# Patch-Prop.net
KiCad netlist of a schematic drawn in EAGLE
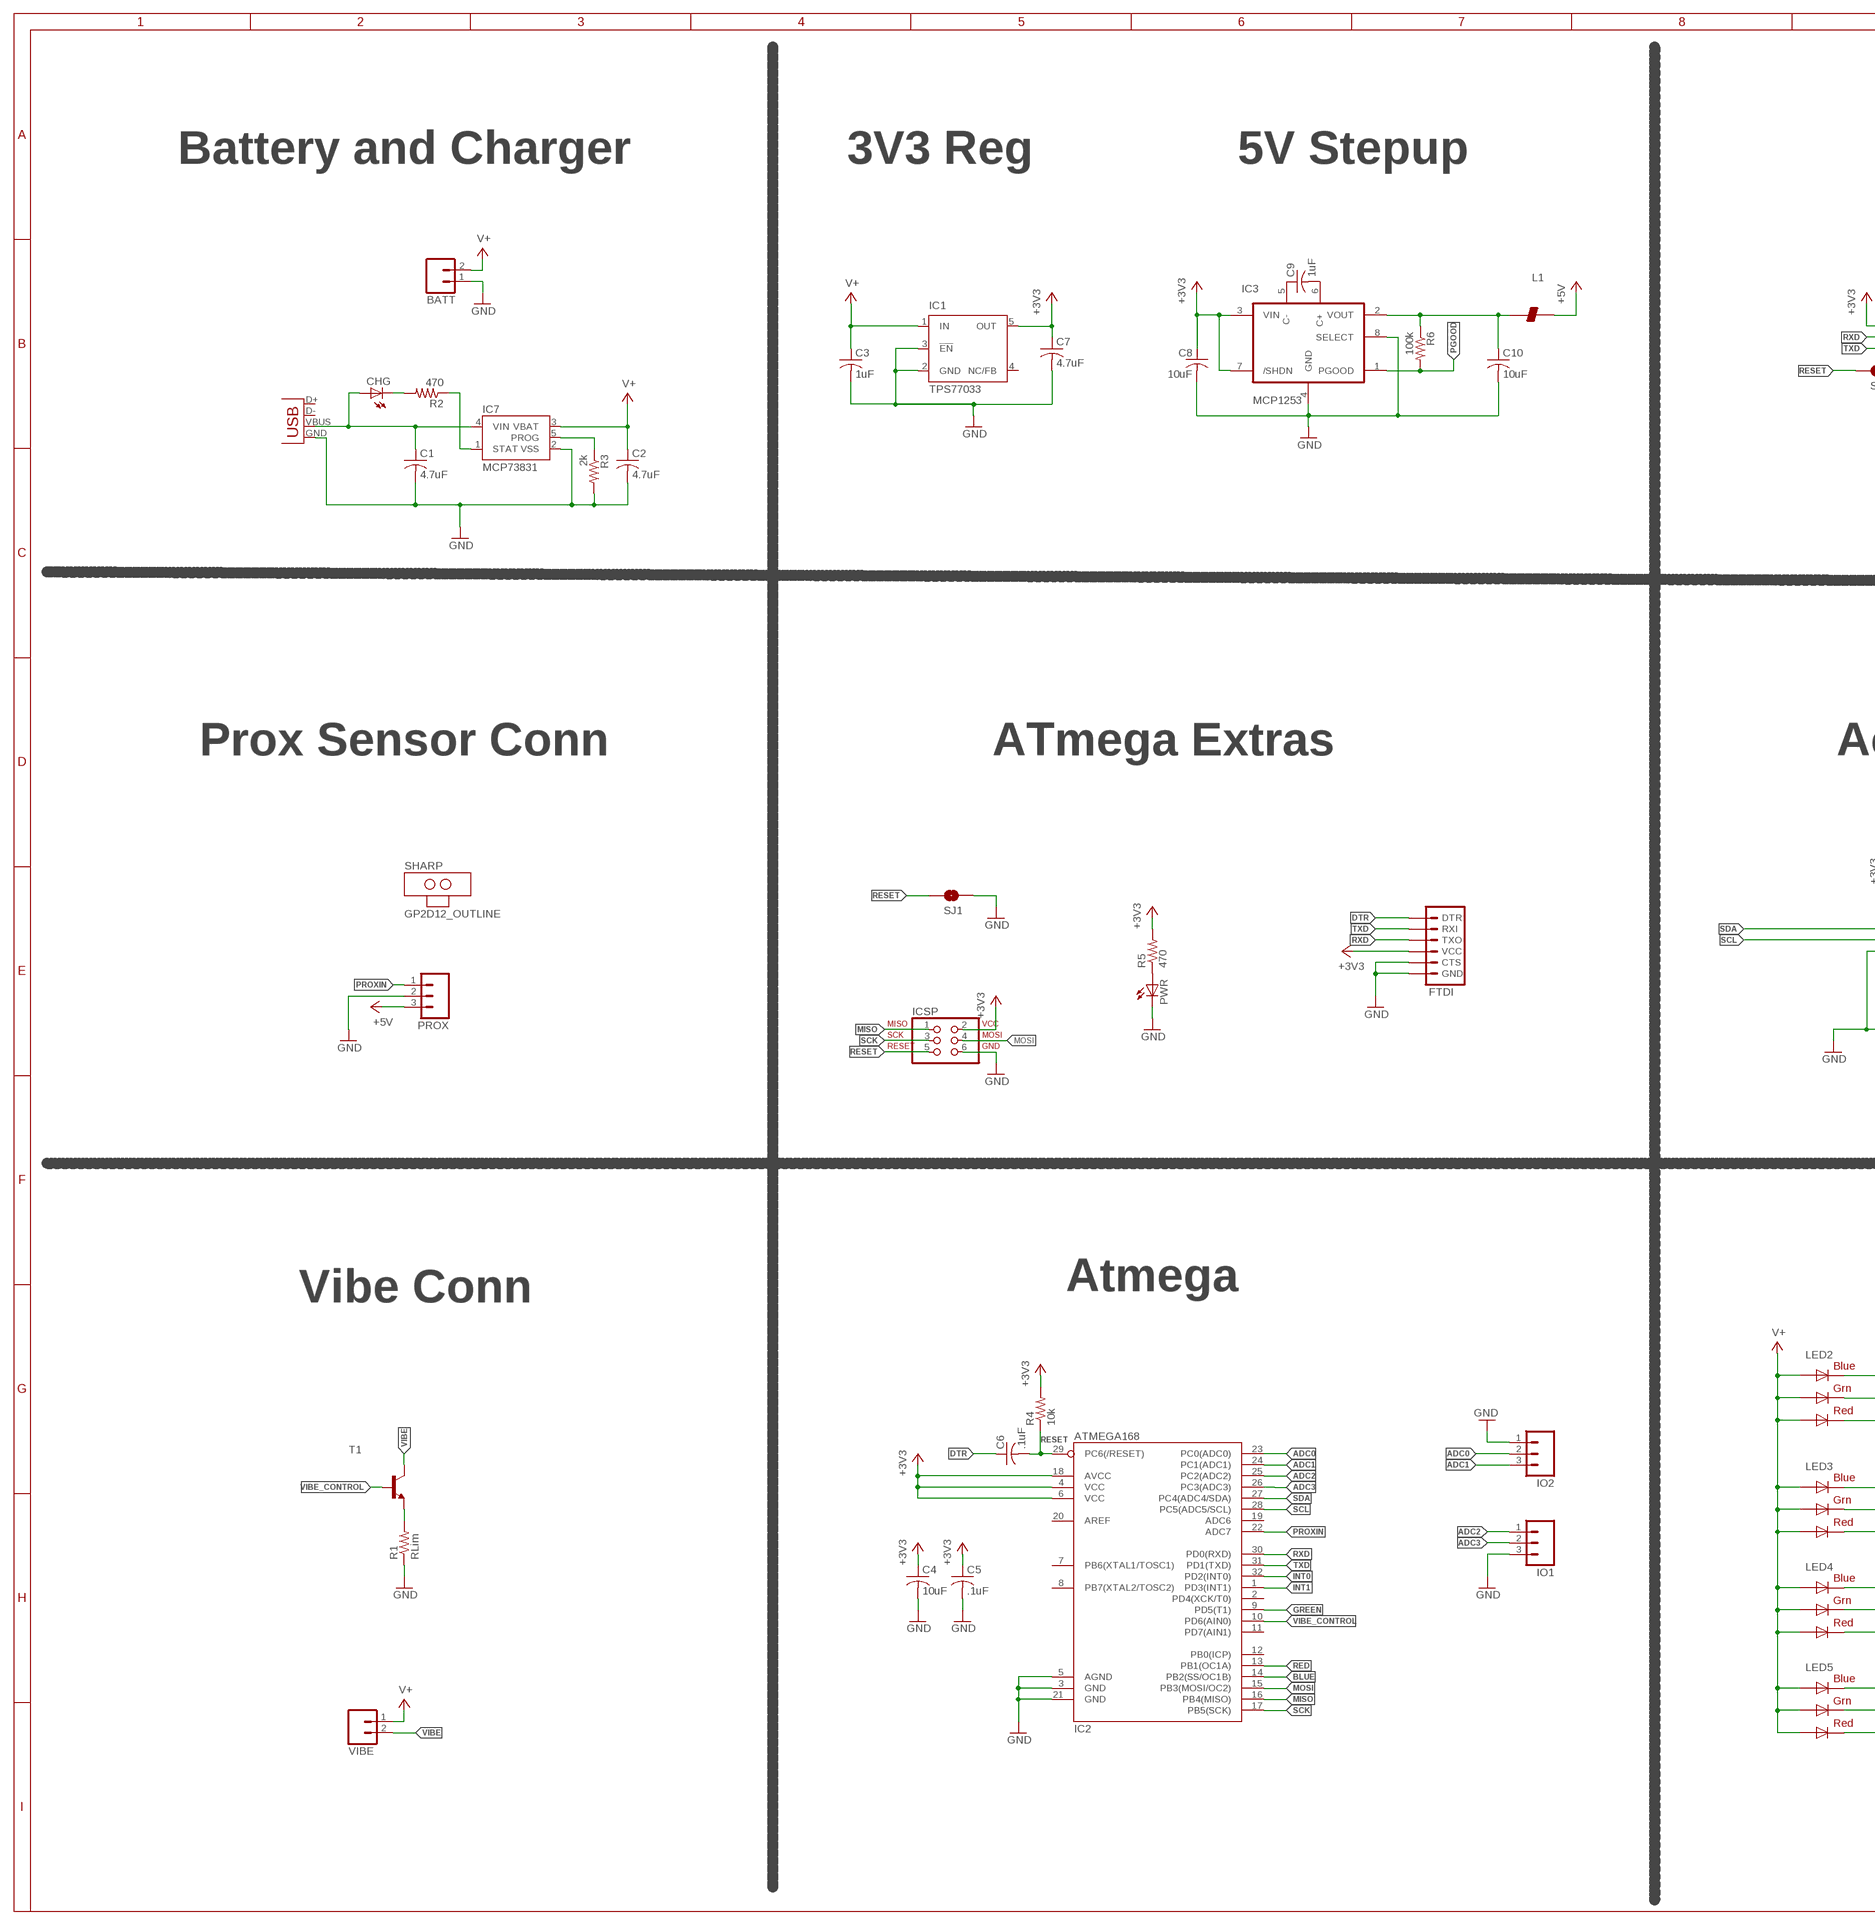
[diagram p0: schematic, sheet 1, part 1 of 2]
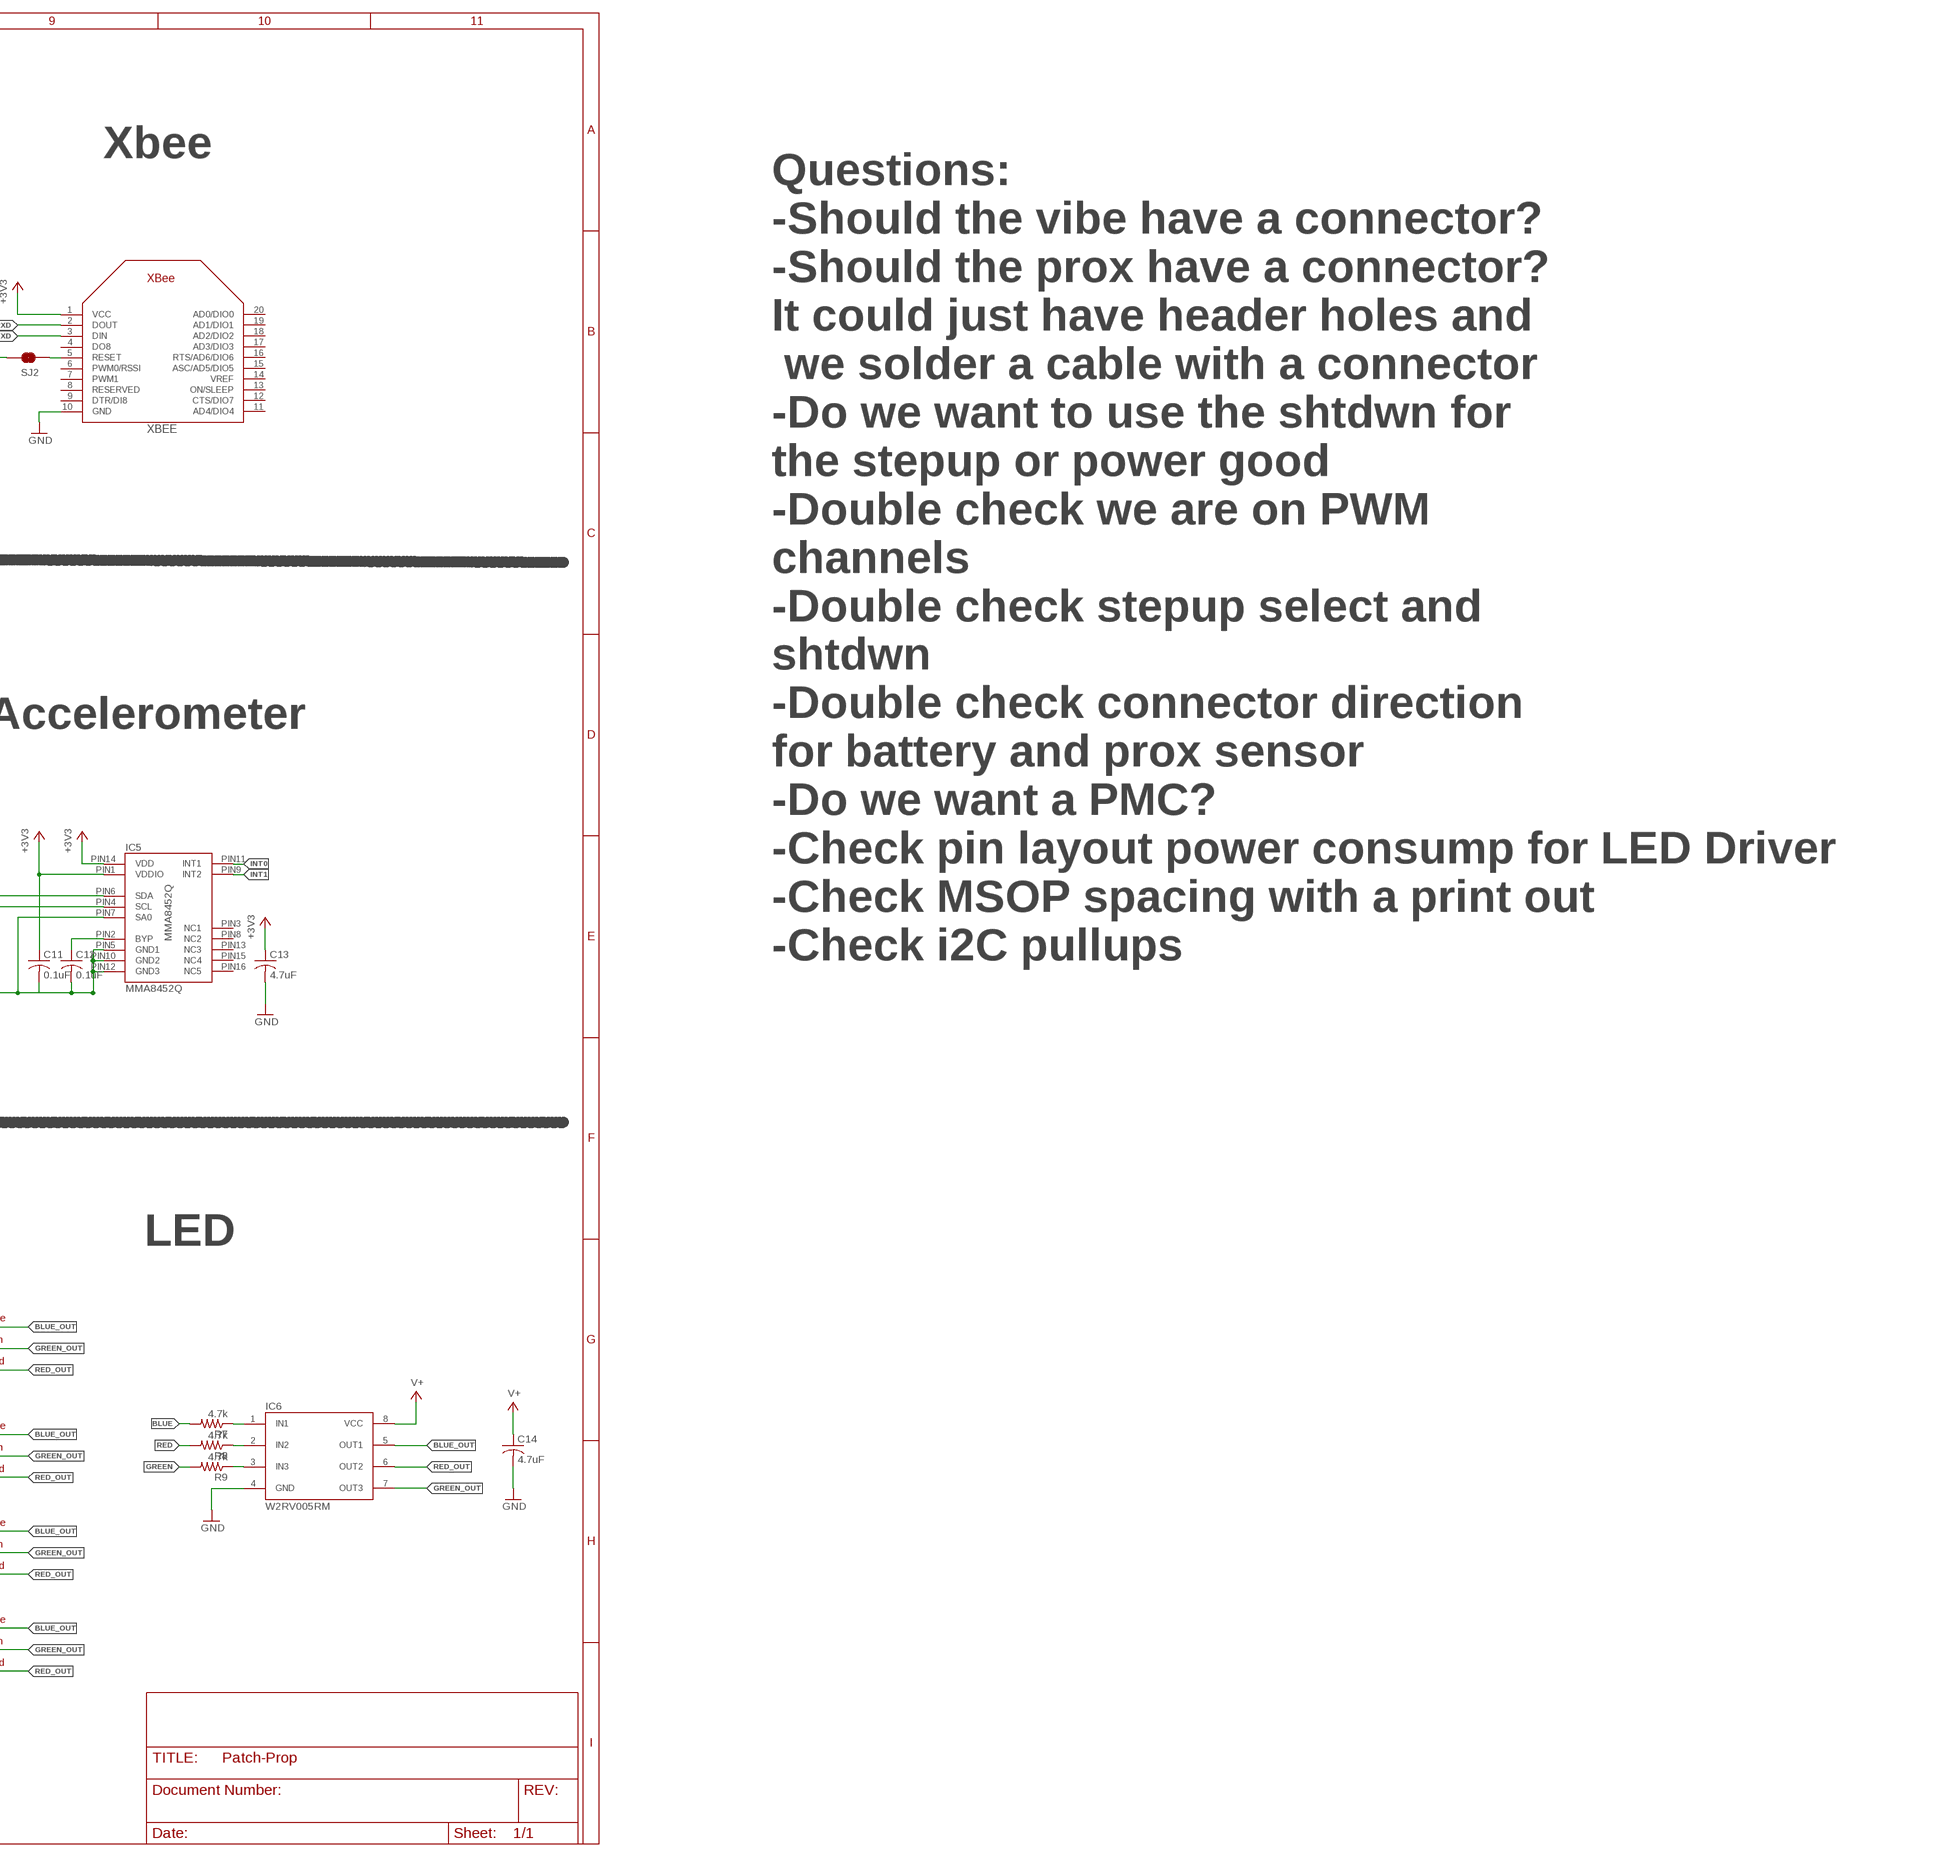
[diagram p1: schematic, sheet 1, part 2 of 2]

(export (version "E")
  (design (tool "Eeschema 10.0.6"))
  (components
    (comp (ref "BATT")
      (value "M02-JST-2MM-SMT")
      (footprint "eagle-import:JST-2-SMD")
      (libsource (lib "eagle-import") (part "M02-JST-2MM-SMT"))
    )
    (comp (ref "C1")
      (value "4.7uF")
      (footprint "eagle-import:C0603")
      (libsource (lib "eagle-import") (part "C-USC0603"))
    )
    (comp (ref "C2")
      (value "4.7uF")
      (footprint "eagle-import:C0603")
      (libsource (lib "eagle-import") (part "C-USC0603"))
    )
    (comp (ref "C3")
      (value "1uF")
      (footprint "eagle-import:C0603")
      (libsource (lib "eagle-import") (part "C-USC0603"))
    )
    (comp (ref "C4")
      (value "10uF")
      (footprint "eagle-import:C0603")
      (libsource (lib "eagle-import") (part "C-USC0603"))
    )
    (comp (ref "C5")
      (value ".1uF")
      (footprint "eagle-import:C0603")
      (libsource (lib "eagle-import") (part "C-USC0603"))
    )
    (comp (ref "C6")
      (value ".1uF")
      (footprint "eagle-import:C0603")
      (libsource (lib "eagle-import") (part "C-USC0603"))
    )
    (comp (ref "C7")
      (value "4.7uF")
      (footprint "eagle-import:C0603")
      (libsource (lib "eagle-import") (part "C-USC0603"))
    )
    (comp (ref "C8")
      (value "10uF")
      (footprint "eagle-import:C0603")
      (libsource (lib "eagle-import") (part "C-USC0603"))
    )
    (comp (ref "C9")
      (value "1uF")
      (footprint "eagle-import:C0603")
      (libsource (lib "eagle-import") (part "C-USC0603"))
    )
    (comp (ref "C10")
      (value "10uF")
      (footprint "eagle-import:C0603")
      (libsource (lib "eagle-import") (part "C-USC0603"))
    )
    (comp (ref "C11")
      (value "0.1uF")
      (footprint "eagle-import:C0603")
      (libsource (lib "eagle-import") (part "C-USC0603"))
    )
    (comp (ref "C12")
      (value "0.1uF")
      (footprint "eagle-import:C0603")
      (libsource (lib "eagle-import") (part "C-USC0603"))
    )
    (comp (ref "C13")
      (value "4.7uF")
      (footprint "eagle-import:C0603")
      (libsource (lib "eagle-import") (part "C-USC0603"))
    )
    (comp (ref "C14")
      (value "4.7uF")
      (footprint "eagle-import:C0603")
      (libsource (lib "eagle-import") (part "C-USC0603"))
    )
    (comp (ref "CHG")
      (value "LEDCHIPLED_0805")
      (footprint "eagle-import:CHIPLED_0805")
      (libsource (lib "eagle-import") (part "LEDCHIPLED_0805"))
    )
    (comp (ref "FTDI")
      (value "ARDUINO_SERIAL_PROGRAMPTH")
      (footprint "eagle-import:1X06")
      (libsource (lib "eagle-import") (part "ARDUINO_SERIAL_PROGRAMPTH"))
    )
    (comp (ref "IC1")
      (value "TPS77033")
      (footprint "eagle-import:SOT23-DBV")
      (fields (field (name "MF") "TEXAS INSTRUMENTS") (field (name "MPN") "TPS77033DBVT"))
      (libsource (lib "eagle-import") (part "TPS77033"))
    )
    (comp (ref "IC2")
      (value "ATMEGA168")
      (footprint "eagle-import:TQFP32-08")
      (libsource (lib "eagle-import") (part "ATMEGA168"))
    )
    (comp (ref "IC3")
      (value "MCP1253")
      (footprint "eagle-import:MSOP8")
      (libsource (lib "eagle-import") (part "MCP1253"))
    )
    (comp (ref "IC5")
      (value "MMA8452Q")
      (footprint "eagle-import:QFN-16")
      (libsource (lib "eagle-import") (part "MMA8452Q"))
    )
    (comp (ref "IC6")
      (value "W2RV005RM")
      (footprint "eagle-import:MSOP8")
      (libsource (lib "eagle-import") (part "W2RV005RM"))
    )
    (comp (ref "IC7")
      (value "MCP73831")
      (footprint "eagle-import:SOT23-5")
      (libsource (lib "eagle-import") (part "MCP73831SMD"))
    )
    (comp (ref "ICSP")
      (value "ISP-AVR910SMD")
      (footprint "eagle-import:2X03_BORDER")
      (libsource (lib "eagle-import") (part "ISP-AVR910SMD"))
    )
    (comp (ref "IO1")
      (value "M03PTH")
      (footprint "eagle-import:1X03")
      (libsource (lib "eagle-import") (part "M03PTH"))
    )
    (comp (ref "IO2")
      (value "M03PTH")
      (footprint "eagle-import:1X03")
      (libsource (lib "eagle-import") (part "M03PTH"))
    )
    (comp (ref "L1")
      (value "BEAD-0805")
      (footprint "eagle-import:0805")
      (libsource (lib "eagle-import") (part "BEAD-0805"))
    )
    (comp (ref "LED2")
      (value "RGBLED5050")
      (footprint "eagle-import:RGBLED5050")
      (libsource (lib "eagle-import") (part "RGBLED5050"))
    )
    (comp (ref "LED3")
      (value "RGBLED5050")
      (footprint "eagle-import:RGBLED5050")
      (libsource (lib "eagle-import") (part "RGBLED5050"))
    )
    (comp (ref "LED4")
      (value "RGBLED5050")
      (footprint "eagle-import:RGBLED5050")
      (libsource (lib "eagle-import") (part "RGBLED5050"))
    )
    (comp (ref "LED5")
      (value "RGBLED5050")
      (footprint "eagle-import:RGBLED5050")
      (libsource (lib "eagle-import") (part "RGBLED5050"))
    )
    (comp (ref "PROX")
      (value "M03PTH")
      (footprint "eagle-import:1X03")
      (libsource (lib "eagle-import") (part "SparkFun-Connectors_M03PTH"))
    )
    (comp (ref "PWR")
      (value "LEDCHIPLED_0805")
      (footprint "eagle-import:CHIPLED_0805")
      (libsource (lib "eagle-import") (part "LEDCHIPLED_0805"))
    )
    (comp (ref "R1")
      (value "RLim")
      (footprint "eagle-import:R0603")
      (libsource (lib "eagle-import") (part "R-US_R0603"))
    )
    (comp (ref "R2")
      (value "470")
      (footprint "eagle-import:R0603")
      (libsource (lib "eagle-import") (part "R-US_R0603"))
    )
    (comp (ref "R3")
      (value "2k")
      (footprint "eagle-import:R0603")
      (libsource (lib "eagle-import") (part "R-US_R0603"))
    )
    (comp (ref "R4")
      (value "10k")
      (footprint "eagle-import:R0603")
      (libsource (lib "eagle-import") (part "R-US_R0603"))
    )
    (comp (ref "R5")
      (value "470")
      (footprint "eagle-import:R0603")
      (libsource (lib "eagle-import") (part "R-US_R0603"))
    )
    (comp (ref "R6")
      (value "100k")
      (footprint "eagle-import:R0603")
      (libsource (lib "eagle-import") (part "R-US_R0603"))
    )
    (comp (ref "R7")
      (value "4.7k")
      (footprint "eagle-import:R0603")
      (libsource (lib "eagle-import") (part "R-US_R0603"))
    )
    (comp (ref "R8")
      (value "4.7k")
      (footprint "eagle-import:R0603")
      (libsource (lib "eagle-import") (part "R-US_R0603"))
    )
    (comp (ref "R9")
      (value "4.7k")
      (footprint "eagle-import:R0603")
      (libsource (lib "eagle-import") (part "R-US_R0603"))
    )
    (comp (ref "SHARP")
      (value "GP2D12_OUTLINE")
      (footprint "eagle-import:GP2D12_OUTLINE")
      (libsource (lib "eagle-import") (part "GP2D12_OUTLINE"))
    )
    (comp (ref "SJ1")
      (value "SOLDERJUMPERNO")
      (footprint "eagle-import:SJ_2S-NO")
      (libsource (lib "eagle-import") (part "SOLDERJUMPERNO"))
    )
    (comp (ref "SJ2")
      (value "SOLDERJUMPERNO")
      (footprint "eagle-import:SJ_2S-NO")
      (libsource (lib "eagle-import") (part "SOLDERJUMPERNO"))
    )
    (comp (ref "T1")
      (value "-NPN-SOT23-EBC")
      (footprint "eagle-import:SOT23-EBC")
      (libsource (lib "eagle-import") (part "-NPN-SOT23-EBC"))
    )
    (comp (ref "USB")
      (value "USBSMD")
      (footprint "eagle-import:USB-MINIB")
      (libsource (lib "eagle-import") (part "USBSMD"))
    )
    (comp (ref "VIBE")
      (value "M02PTH")
      (footprint "eagle-import:1X02")
      (libsource (lib "eagle-import") (part "M02PTH"))
    )
    (comp (ref "XBEE")
      (value "XBEE")
      (footprint "eagle-import:XBEE")
      (libsource (lib "eagle-import") (part "XBEE"))
    )
  )
  (nets
    (net (code "1") (name "+3V3") (class "Default")
      (node (ref "C11") (pin "1") (pinfunction "1_1") (pintype "passive"))
      (node (ref "C13") (pin "1") (pinfunction "1_1") (pintype "passive"))
      (node (ref "C4") (pin "1") (pinfunction "1_1") (pintype "passive"))
      (node (ref "C5") (pin "1") (pinfunction "1_1") (pintype "passive"))
      (node (ref "C7") (pin "1") (pinfunction "1_1") (pintype "passive"))
      (node (ref "C8") (pin "1") (pinfunction "1_1") (pintype "passive"))
      (node (ref "FTDI") (pin "4") (pinfunction "VCC_4") (pintype "passive"))
      (node (ref "IC1") (pin "5") (pinfunction "OUT_5") (pintype "passive"))
      (node (ref "IC2") (pin "18") (pinfunction "AVCC_18") (pintype "bidirectional"))
      (node (ref "IC2") (pin "4") (pinfunction "VCC_4") (pintype "bidirectional"))
      (node (ref "IC2") (pin "6") (pinfunction "VCC_6") (pintype "bidirectional"))
      (node (ref "IC3") (pin "3") (pinfunction "VIN_3") (pintype "bidirectional"))
      (node (ref "IC3") (pin "7") (pinfunction "/SHDN_7") (pintype "bidirectional"))
      (node (ref "IC5") (pin "PIN1") (pinfunction "VDDIO_PIN1") (pintype "bidirectional"))
      (node (ref "IC5") (pin "PIN14") (pinfunction "VDD_PIN14") (pintype "bidirectional"))
      (node (ref "ICSP") (pin "2") (pinfunction "2_2") (pintype "passive"))
      (node (ref "R4") (pin "2") (pinfunction "2_2") (pintype "passive"))
      (node (ref "R5") (pin "2") (pinfunction "2_2") (pintype "passive"))
      (node (ref "XBEE") (pin "1") (pinfunction "VCC_1") (pintype "power_in"))
    )
    (net (code "2") (name "+5V") (class "Default")
      (node (ref "L1") (pin "2") (pinfunction "P$2_2") (pintype "passive"))
      (node (ref "PROX") (pin "3") (pinfunction "3_3") (pintype "passive"))
    )
    (net (code "3") (name "ADC0") (class "Default")
      (node (ref "IC2") (pin "23") (pinfunction "PC0(ADC0)_23") (pintype "bidirectional"))
      (node (ref "IO2") (pin "2") (pinfunction "2_2") (pintype "passive"))
    )
    (net (code "4") (name "ADC1") (class "Default")
      (node (ref "IC2") (pin "24") (pinfunction "PC1(ADC1)_24") (pintype "bidirectional"))
      (node (ref "IO2") (pin "3") (pinfunction "3_3") (pintype "passive"))
    )
    (net (code "5") (name "ADC2") (class "Default")
      (node (ref "IC2") (pin "25") (pinfunction "PC2(ADC2)_25") (pintype "bidirectional"))
      (node (ref "IO1") (pin "1") (pinfunction "1_1") (pintype "passive"))
    )
    (net (code "6") (name "ADC3") (class "Default")
      (node (ref "IC2") (pin "26") (pinfunction "PC3(ADC3)_26") (pintype "bidirectional"))
      (node (ref "IO1") (pin "2") (pinfunction "2_2") (pintype "passive"))
    )
    (net (code "7") (name "BLUE") (class "Default")
      (node (ref "IC2") (pin "14") (pinfunction "PB2(SS/OC1B)_14") (pintype "bidirectional"))
      (node (ref "R7") (pin "2") (pinfunction "2_2") (pintype "passive"))
    )
    (net (code "8") (name "BLUE_OUT") (class "Default")
      (node (ref "IC6") (pin "5") (pinfunction "OUT1_5") (pintype "output"))
      (node (ref "LED2") (pin "4") (pinfunction "BLUE_C_4") (pintype "bidirectional"))
      (node (ref "LED3") (pin "4") (pinfunction "BLUE_C_4") (pintype "bidirectional"))
      (node (ref "LED4") (pin "4") (pinfunction "BLUE_C_4") (pintype "bidirectional"))
      (node (ref "LED5") (pin "4") (pinfunction "BLUE_C_4") (pintype "bidirectional"))
    )
    (net (code "9") (name "DTR") (class "Default")
      (node (ref "C6") (pin "1") (pinfunction "1_1") (pintype "passive"))
      (node (ref "FTDI") (pin "1") (pinfunction "DTR_1") (pintype "passive"))
    )
    (net (code "10") (name "GND") (class "Default")
      (node (ref "BATT") (pin "1") (pinfunction "2_1") (pintype "passive"))
      (node (ref "C1") (pin "2") (pinfunction "2_2") (pintype "passive"))
      (node (ref "C10") (pin "2") (pinfunction "2_2") (pintype "passive"))
      (node (ref "C11") (pin "2") (pinfunction "2_2") (pintype "passive"))
      (node (ref "C12") (pin "2") (pinfunction "2_2") (pintype "passive"))
      (node (ref "C13") (pin "2") (pinfunction "2_2") (pintype "passive"))
      (node (ref "C14") (pin "2") (pinfunction "2_2") (pintype "passive"))
      (node (ref "C2") (pin "2") (pinfunction "2_2") (pintype "passive"))
      (node (ref "C3") (pin "2") (pinfunction "2_2") (pintype "passive"))
      (node (ref "C4") (pin "2") (pinfunction "2_2") (pintype "passive"))
      (node (ref "C5") (pin "2") (pinfunction "2_2") (pintype "passive"))
      (node (ref "C7") (pin "2") (pinfunction "2_2") (pintype "passive"))
      (node (ref "C8") (pin "2") (pinfunction "2_2") (pintype "passive"))
      (node (ref "FTDI") (pin "5") (pinfunction "CTS_5") (pintype "passive"))
      (node (ref "FTDI") (pin "6") (pinfunction "GND_6") (pintype "passive"))
      (node (ref "IC1") (pin "2") (pinfunction "GND_2") (pintype "power_in"))
      (node (ref "IC1") (pin "3") (pinfunction "~{EN}_3") (pintype "input"))
      (node (ref "IC2") (pin "21") (pinfunction "GND_21") (pintype "bidirectional"))
      (node (ref "IC2") (pin "3") (pinfunction "GND_3") (pintype "bidirectional"))
      (node (ref "IC2") (pin "5") (pinfunction "AGND_5") (pintype "bidirectional"))
      (node (ref "IC3") (pin "4") (pinfunction "GND_4") (pintype "bidirectional"))
      (node (ref "IC3") (pin "8") (pinfunction "SELECT_8") (pintype "bidirectional"))
      (node (ref "IC5") (pin "PIN10") (pinfunction "GND2_PIN10") (pintype "bidirectional"))
      (node (ref "IC5") (pin "PIN12") (pinfunction "GND3_PIN12") (pintype "bidirectional"))
      (node (ref "IC5") (pin "PIN5") (pinfunction "GND1_PIN5") (pintype "bidirectional"))
      (node (ref "IC5") (pin "PIN7") (pinfunction "SA0_PIN7") (pintype "bidirectional"))
      (node (ref "IC6") (pin "4") (pinfunction "GND_4") (pintype "bidirectional"))
      (node (ref "IC7") (pin "2") (pinfunction "VSS_2") (pintype "power_in"))
      (node (ref "ICSP") (pin "6") (pinfunction "6_6") (pintype "passive"))
      (node (ref "IO1") (pin "3") (pinfunction "3_3") (pintype "passive"))
      (node (ref "IO2") (pin "1") (pinfunction "1_1") (pintype "passive"))
      (node (ref "PROX") (pin "2") (pinfunction "2_2") (pintype "passive"))
      (node (ref "PWR") (pin "C") (pinfunction "C_C") (pintype "passive"))
      (node (ref "R1") (pin "1") (pinfunction "1_1") (pintype "passive"))
      (node (ref "R3") (pin "2") (pinfunction "2_2") (pintype "passive"))
      (node (ref "SJ1") (pin "1") (pinfunction "1_1") (pintype "passive"))
      (node (ref "USB") (pin "GND") (pinfunction "GND_GND") (pintype "bidirectional"))
      (node (ref "XBEE") (pin "10") (pinfunction "GND_10") (pintype "power_in"))
    )
    (net (code "11") (name "GREEN") (class "Default")
      (node (ref "IC2") (pin "9") (pinfunction "PD5(T1)_9") (pintype "bidirectional"))
      (node (ref "R9") (pin "2") (pinfunction "2_2") (pintype "passive"))
    )
    (net (code "12") (name "GREEN_OUT") (class "Default")
      (node (ref "IC6") (pin "7") (pinfunction "OUT3_7") (pintype "output"))
      (node (ref "LED2") (pin "6") (pinfunction "GREEN_C_6") (pintype "bidirectional"))
      (node (ref "LED3") (pin "6") (pinfunction "GREEN_C_6") (pintype "bidirectional"))
      (node (ref "LED4") (pin "6") (pinfunction "GREEN_C_6") (pintype "bidirectional"))
      (node (ref "LED5") (pin "6") (pinfunction "GREEN_C_6") (pintype "bidirectional"))
    )
    (net (code "13") (name "INT0") (class "Default")
      (node (ref "IC2") (pin "32") (pinfunction "PD2(INT0)_32") (pintype "bidirectional"))
      (node (ref "IC5") (pin "PIN11") (pinfunction "INT1_PIN11") (pintype "bidirectional"))
    )
    (net (code "14") (name "INT1") (class "Default")
      (node (ref "IC2") (pin "1") (pinfunction "PD3(INT1)_1") (pintype "bidirectional"))
      (node (ref "IC5") (pin "PIN9") (pinfunction "INT2_PIN9") (pintype "bidirectional"))
    )
    (net (code "15") (name "MISO") (class "Default")
      (node (ref "IC2") (pin "16") (pinfunction "PB4(MISO)_16") (pintype "bidirectional"))
      (node (ref "ICSP") (pin "1") (pinfunction "1_1") (pintype "passive"))
    )
    (net (code "16") (name "MOSI") (class "Default")
      (node (ref "IC2") (pin "15") (pinfunction "PB3(MOSI/OC2)_15") (pintype "bidirectional"))
      (node (ref "ICSP") (pin "4") (pinfunction "4_4") (pintype "passive"))
    )
    (net (code "17") (name "Net-(CHG-PadC)") (class "Default")
      (node (ref "CHG") (pin "C") (pinfunction "C_C") (pintype "passive"))
      (node (ref "R2") (pin "2") (pinfunction "2_2") (pintype "passive"))
    )
    (net (code "18") (name "Net-(IC3-C+)") (class "Default")
      (node (ref "C9") (pin "2") (pinfunction "2_2") (pintype "passive"))
      (node (ref "IC3") (pin "6") (pinfunction "C+_6") (pintype "bidirectional"))
    )
    (net (code "19") (name "Net-(IC3-C-)") (class "Default")
      (node (ref "C9") (pin "1") (pinfunction "1_1") (pintype "passive"))
      (node (ref "IC3") (pin "5") (pinfunction "C-_5") (pintype "bidirectional"))
    )
    (net (code "20") (name "Net-(IC3-VOUT)") (class "Default")
      (node (ref "C10") (pin "1") (pinfunction "1_1") (pintype "passive"))
      (node (ref "IC3") (pin "2") (pinfunction "VOUT_2") (pintype "bidirectional"))
      (node (ref "L1") (pin "1") (pinfunction "P$1_1") (pintype "passive"))
      (node (ref "R6") (pin "1") (pinfunction "1_1") (pintype "passive"))
    )
    (net (code "21") (name "Net-(IC5-BYP)") (class "Default")
      (node (ref "C12") (pin "1") (pinfunction "1_1") (pintype "passive"))
      (node (ref "IC5") (pin "PIN2") (pinfunction "BYP_PIN2") (pintype "bidirectional"))
    )
    (net (code "22") (name "Net-(IC6-IN1)") (class "Default")
      (node (ref "IC6") (pin "1") (pinfunction "IN1_1") (pintype "input"))
      (node (ref "R7") (pin "1") (pinfunction "1_1") (pintype "passive"))
    )
    (net (code "23") (name "Net-(IC6-IN2)") (class "Default")
      (node (ref "IC6") (pin "2") (pinfunction "IN2_2") (pintype "input"))
      (node (ref "R8") (pin "1") (pinfunction "1_1") (pintype "passive"))
    )
    (net (code "24") (name "Net-(IC6-IN3)") (class "Default")
      (node (ref "IC6") (pin "3") (pinfunction "IN3_3") (pintype "input"))
      (node (ref "R9") (pin "1") (pinfunction "1_1") (pintype "passive"))
    )
    (net (code "25") (name "Net-(IC7-PROG)") (class "Default")
      (node (ref "IC7") (pin "5") (pinfunction "PROG_5") (pintype "input"))
      (node (ref "R3") (pin "1") (pinfunction "1_1") (pintype "passive"))
    )
    (net (code "26") (name "Net-(IC7-STAT)") (class "Default")
      (node (ref "IC7") (pin "1") (pinfunction "STAT_1") (pintype "output"))
      (node (ref "R2") (pin "1") (pinfunction "1_1") (pintype "passive"))
    )
    (net (code "27") (name "Net-(IC7-VIN)") (class "Default")
      (node (ref "C1") (pin "1") (pinfunction "1_1") (pintype "passive"))
      (node (ref "CHG") (pin "A") (pinfunction "A_A") (pintype "passive"))
      (node (ref "IC7") (pin "4") (pinfunction "VIN_4") (pintype "power_in"))
      (node (ref "USB") (pin "VBUS") (pinfunction "VBUS_VBUS") (pintype "bidirectional"))
    )
    (net (code "28") (name "Net-(PWR-PadA)") (class "Default")
      (node (ref "PWR") (pin "A") (pinfunction "A_A") (pintype "passive"))
      (node (ref "R5") (pin "1") (pinfunction "1_1") (pintype "passive"))
    )
    (net (code "29") (name "Net-(R1-Pad2)") (class "Default")
      (node (ref "R1") (pin "2") (pinfunction "2_2") (pintype "passive"))
      (node (ref "T1") (pin "E") (pinfunction "E_E") (pintype "passive"))
    )
    (net (code "30") (name "Net-(XBEE-RESET)") (class "Default")
      (node (ref "SJ2") (pin "1") (pinfunction "1_1") (pintype "passive"))
      (node (ref "XBEE") (pin "5") (pinfunction "RESET_5") (pintype "input"))
    )
    (net (code "31") (name "PGOOD") (class "Default")
      (node (ref "IC3") (pin "1") (pinfunction "PGOOD_1") (pintype "bidirectional"))
      (node (ref "R6") (pin "2") (pinfunction "2_2") (pintype "passive"))
    )
    (net (code "32") (name "PROXIN") (class "Default")
      (node (ref "IC2") (pin "22") (pinfunction "ADC7_22") (pintype "bidirectional"))
      (node (ref "PROX") (pin "1") (pinfunction "1_1") (pintype "passive"))
    )
    (net (code "33") (name "RED") (class "Default")
      (node (ref "IC2") (pin "13") (pinfunction "PB1(OC1A)_13") (pintype "bidirectional"))
      (node (ref "R8") (pin "2") (pinfunction "2_2") (pintype "passive"))
    )
    (net (code "34") (name "RED_OUT") (class "Default")
      (node (ref "IC6") (pin "6") (pinfunction "OUT2_6") (pintype "output"))
      (node (ref "LED2") (pin "5") (pinfunction "RED_C_5") (pintype "bidirectional"))
      (node (ref "LED3") (pin "5") (pinfunction "RED_C_5") (pintype "bidirectional"))
      (node (ref "LED4") (pin "5") (pinfunction "RED_C_5") (pintype "bidirectional"))
      (node (ref "LED5") (pin "5") (pinfunction "RED_C_5") (pintype "bidirectional"))
    )
    (net (code "35") (name "RESET") (class "Default")
      (node (ref "C6") (pin "2") (pinfunction "2_2") (pintype "passive"))
      (node (ref "IC2") (pin "29") (pinfunction "PC6(/RESET)_29") (pintype "bidirectional"))
      (node (ref "ICSP") (pin "5") (pinfunction "5_5") (pintype "passive"))
      (node (ref "R4") (pin "1") (pinfunction "1_1") (pintype "passive"))
      (node (ref "SJ1") (pin "2") (pinfunction "2_2") (pintype "passive"))
      (node (ref "SJ2") (pin "2") (pinfunction "2_2") (pintype "passive"))
    )
    (net (code "36") (name "RXD") (class "Default")
      (node (ref "FTDI") (pin "3") (pinfunction "TXO_3") (pintype "passive"))
      (node (ref "IC2") (pin "30") (pinfunction "PD0(RXD)_30") (pintype "bidirectional"))
      (node (ref "XBEE") (pin "2") (pinfunction "DOUT_2") (pintype "output"))
    )
    (net (code "37") (name "SCK") (class "Default")
      (node (ref "IC2") (pin "17") (pinfunction "PB5(SCK)_17") (pintype "bidirectional"))
      (node (ref "ICSP") (pin "3") (pinfunction "3_3") (pintype "passive"))
    )
    (net (code "38") (name "SCL") (class "Default")
      (node (ref "IC2") (pin "28") (pinfunction "PC5(ADC5/SCL)_28") (pintype "bidirectional"))
      (node (ref "IC5") (pin "PIN4") (pinfunction "SCL_PIN4") (pintype "bidirectional"))
    )
    (net (code "39") (name "SDA") (class "Default")
      (node (ref "IC2") (pin "27") (pinfunction "PC4(ADC4/SDA)_27") (pintype "bidirectional"))
      (node (ref "IC5") (pin "PIN6") (pinfunction "SDA_PIN6") (pintype "bidirectional"))
    )
    (net (code "40") (name "TXD") (class "Default")
      (node (ref "FTDI") (pin "2") (pinfunction "RXI_2") (pintype "passive"))
      (node (ref "IC2") (pin "31") (pinfunction "PD1(TXD)_31") (pintype "bidirectional"))
      (node (ref "XBEE") (pin "3") (pinfunction "DIN_3") (pintype "input"))
    )
    (net (code "41") (name "V+") (class "Default")
      (node (ref "BATT") (pin "2") (pinfunction "1_2") (pintype "passive"))
      (node (ref "C14") (pin "1") (pinfunction "1_1") (pintype "passive"))
      (node (ref "C2") (pin "1") (pinfunction "1_1") (pintype "passive"))
      (node (ref "C3") (pin "1") (pinfunction "1_1") (pintype "passive"))
      (node (ref "IC1") (pin "1") (pinfunction "IN_1") (pintype "input"))
      (node (ref "IC6") (pin "8") (pinfunction "VCC_8") (pintype "bidirectional"))
      (node (ref "IC7") (pin "3") (pinfunction "VBAT_3") (pintype "power_in"))
      (node (ref "LED2") (pin "1") (pinfunction "GREEN_A_1") (pintype "bidirectional"))
      (node (ref "LED2") (pin "2") (pinfunction "RED_A_2") (pintype "bidirectional"))
      (node (ref "LED2") (pin "3") (pinfunction "BLUE_A_3") (pintype "bidirectional"))
      (node (ref "LED3") (pin "1") (pinfunction "GREEN_A_1") (pintype "bidirectional"))
      (node (ref "LED3") (pin "2") (pinfunction "RED_A_2") (pintype "bidirectional"))
      (node (ref "LED3") (pin "3") (pinfunction "BLUE_A_3") (pintype "bidirectional"))
      (node (ref "LED4") (pin "1") (pinfunction "GREEN_A_1") (pintype "bidirectional"))
      (node (ref "LED4") (pin "2") (pinfunction "RED_A_2") (pintype "bidirectional"))
      (node (ref "LED4") (pin "3") (pinfunction "BLUE_A_3") (pintype "bidirectional"))
      (node (ref "LED5") (pin "1") (pinfunction "GREEN_A_1") (pintype "bidirectional"))
      (node (ref "LED5") (pin "2") (pinfunction "RED_A_2") (pintype "bidirectional"))
      (node (ref "LED5") (pin "3") (pinfunction "BLUE_A_3") (pintype "bidirectional"))
      (node (ref "VIBE") (pin "1") (pinfunction "1_1") (pintype "passive"))
    )
    (net (code "42") (name "VIBE") (class "Default")
      (node (ref "T1") (pin "C") (pinfunction "C_C") (pintype "passive"))
      (node (ref "VIBE") (pin "2") (pinfunction "2_2") (pintype "passive"))
    )
    (net (code "43") (name "VIBE_CONTROL") (class "Default")
      (node (ref "IC2") (pin "10") (pinfunction "PD6(AIN0)_10") (pintype "bidirectional"))
      (node (ref "T1") (pin "B") (pinfunction "B_B") (pintype "passive"))
    )
    (net (code "44") (name "unconnected-(IC1-NC{slash}FB-Pad4)") (class "Default")
      (node (ref "IC1") (pin "4") (pinfunction "NC/FB_4") (pintype "passive"))
    )
    (net (code "45") (name "unconnected-(IC2-ADC6-Pad19)") (class "Default")
      (node (ref "IC2") (pin "19") (pinfunction "ADC6_19") (pintype "bidirectional"))
    )
    (net (code "46") (name "unconnected-(IC2-AREF-Pad20)") (class "Default")
      (node (ref "IC2") (pin "20") (pinfunction "AREF_20") (pintype "bidirectional"))
    )
    (net (code "47") (name "unconnected-(IC2-PB0(ICP)-Pad12)") (class "Default")
      (node (ref "IC2") (pin "12") (pinfunction "PB0(ICP)_12") (pintype "bidirectional"))
    )
    (net (code "48") (name "unconnected-(IC2-PB6(XTAL1{slash}TOSC1)-Pad7)") (class "Default")
      (node (ref "IC2") (pin "7") (pinfunction "PB6(XTAL1/TOSC1)_7") (pintype "bidirectional"))
    )
    (net (code "49") (name "unconnected-(IC2-PB7(XTAL2{slash}TOSC2)-Pad8)") (class "Default")
      (node (ref "IC2") (pin "8") (pinfunction "PB7(XTAL2/TOSC2)_8") (pintype "bidirectional"))
    )
    (net (code "50") (name "unconnected-(IC2-PD4(XCK{slash}T0)-Pad2)") (class "Default")
      (node (ref "IC2") (pin "2") (pinfunction "PD4(XCK/T0)_2") (pintype "bidirectional"))
    )
    (net (code "51") (name "unconnected-(IC2-PD7(AIN1)-Pad11)") (class "Default")
      (node (ref "IC2") (pin "11") (pinfunction "PD7(AIN1)_11") (pintype "bidirectional"))
    )
    (net (code "52") (name "unconnected-(IC5-NC1-PadPIN3)") (class "Default")
      (node (ref "IC5") (pin "PIN3") (pinfunction "NC1_PIN3") (pintype "bidirectional"))
    )
    (net (code "53") (name "unconnected-(IC5-NC2-PadPIN8)") (class "Default")
      (node (ref "IC5") (pin "PIN8") (pinfunction "NC2_PIN8") (pintype "bidirectional"))
    )
    (net (code "54") (name "unconnected-(IC5-NC3-PadPIN13)") (class "Default")
      (node (ref "IC5") (pin "PIN13") (pinfunction "NC3_PIN13") (pintype "bidirectional"))
    )
    (net (code "55") (name "unconnected-(IC5-NC4-PadPIN15)") (class "Default")
      (node (ref "IC5") (pin "PIN15") (pinfunction "NC4_PIN15") (pintype "bidirectional"))
    )
    (net (code "56") (name "unconnected-(IC5-NC5-PadPIN16)") (class "Default")
      (node (ref "IC5") (pin "PIN16") (pinfunction "NC5_PIN16") (pintype "bidirectional"))
    )
    (net (code "57") (name "unconnected-(USB-PadD+)") (class "Default")
      (node (ref "USB") (pin "D+") (pinfunction "D+_D+") (pintype "bidirectional"))
    )
    (net (code "58") (name "unconnected-(USB-PadD-)") (class "Default")
      (node (ref "USB") (pin "D-") (pinfunction "D-_D-") (pintype "bidirectional"))
    )
    (net (code "59") (name "unconnected-(XBEE-AD0{slash}DIO0-Pad20)") (class "Default")
      (node (ref "XBEE") (pin "20") (pinfunction "AD0/DIO0_20") (pintype "bidirectional"))
    )
    (net (code "60") (name "unconnected-(XBEE-AD1{slash}DIO1-Pad19)") (class "Default")
      (node (ref "XBEE") (pin "19") (pinfunction "AD1/DIO1_19") (pintype "bidirectional"))
    )
    (net (code "61") (name "unconnected-(XBEE-AD2{slash}DIO2-Pad18)") (class "Default")
      (node (ref "XBEE") (pin "18") (pinfunction "AD2/DIO2_18") (pintype "bidirectional"))
    )
    (net (code "62") (name "unconnected-(XBEE-AD3{slash}DIO3-Pad17)") (class "Default")
      (node (ref "XBEE") (pin "17") (pinfunction "AD3/DIO3_17") (pintype "bidirectional"))
    )
    (net (code "63") (name "unconnected-(XBEE-AD4{slash}DIO4-Pad11)") (class "Default")
      (node (ref "XBEE") (pin "11") (pinfunction "AD4/DIO4_11") (pintype "bidirectional"))
    )
    (net (code "64") (name "unconnected-(XBEE-ASC{slash}AD5{slash}DIO5-Pad15)") (class "Default")
      (node (ref "XBEE") (pin "15") (pinfunction "ASC/AD5/DIO5_15") (pintype "bidirectional"))
    )
    (net (code "65") (name "unconnected-(XBEE-CTS{slash}DIO7-Pad12)") (class "Default")
      (node (ref "XBEE") (pin "12") (pinfunction "CTS/DIO7_12") (pintype "bidirectional"))
    )
    (net (code "66") (name "unconnected-(XBEE-DO8-Pad4)") (class "Default")
      (node (ref "XBEE") (pin "4") (pinfunction "DO8_4") (pintype "output"))
    )
    (net (code "67") (name "unconnected-(XBEE-DTR{slash}DI8-Pad9)") (class "Default")
      (node (ref "XBEE") (pin "9") (pinfunction "DTR/DI8_9") (pintype "input"))
    )
    (net (code "68") (name "unconnected-(XBEE-ON{slash}SLEEP-Pad13)") (class "Default")
      (node (ref "XBEE") (pin "13") (pinfunction "ON/SLEEP_13") (pintype "output"))
    )
    (net (code "69") (name "unconnected-(XBEE-PWM0{slash}RSSI-Pad6)") (class "Default")
      (node (ref "XBEE") (pin "6") (pinfunction "PWM0/RSSI_6") (pintype "output"))
    )
    (net (code "70") (name "unconnected-(XBEE-PWM1-Pad7)") (class "Default")
      (node (ref "XBEE") (pin "7") (pinfunction "PWM1_7") (pintype "output"))
    )
    (net (code "71") (name "unconnected-(XBEE-RESERVED-Pad8)") (class "Default")
      (node (ref "XBEE") (pin "8") (pinfunction "RESERVED_8") (pintype "no_connect"))
    )
    (net (code "72") (name "unconnected-(XBEE-RTS{slash}AD6{slash}DIO6-Pad16)") (class "Default")
      (node (ref "XBEE") (pin "16") (pinfunction "RTS/AD6/DIO6_16") (pintype "bidirectional"))
    )
    (net (code "73") (name "unconnected-(XBEE-VREF-Pad14)") (class "Default")
      (node (ref "XBEE") (pin "14") (pinfunction "VREF_14") (pintype "input"))
    )
  )
)
